# platine_gesamt_V03.net
KiCad netlist of a schematic drawn in EAGLE
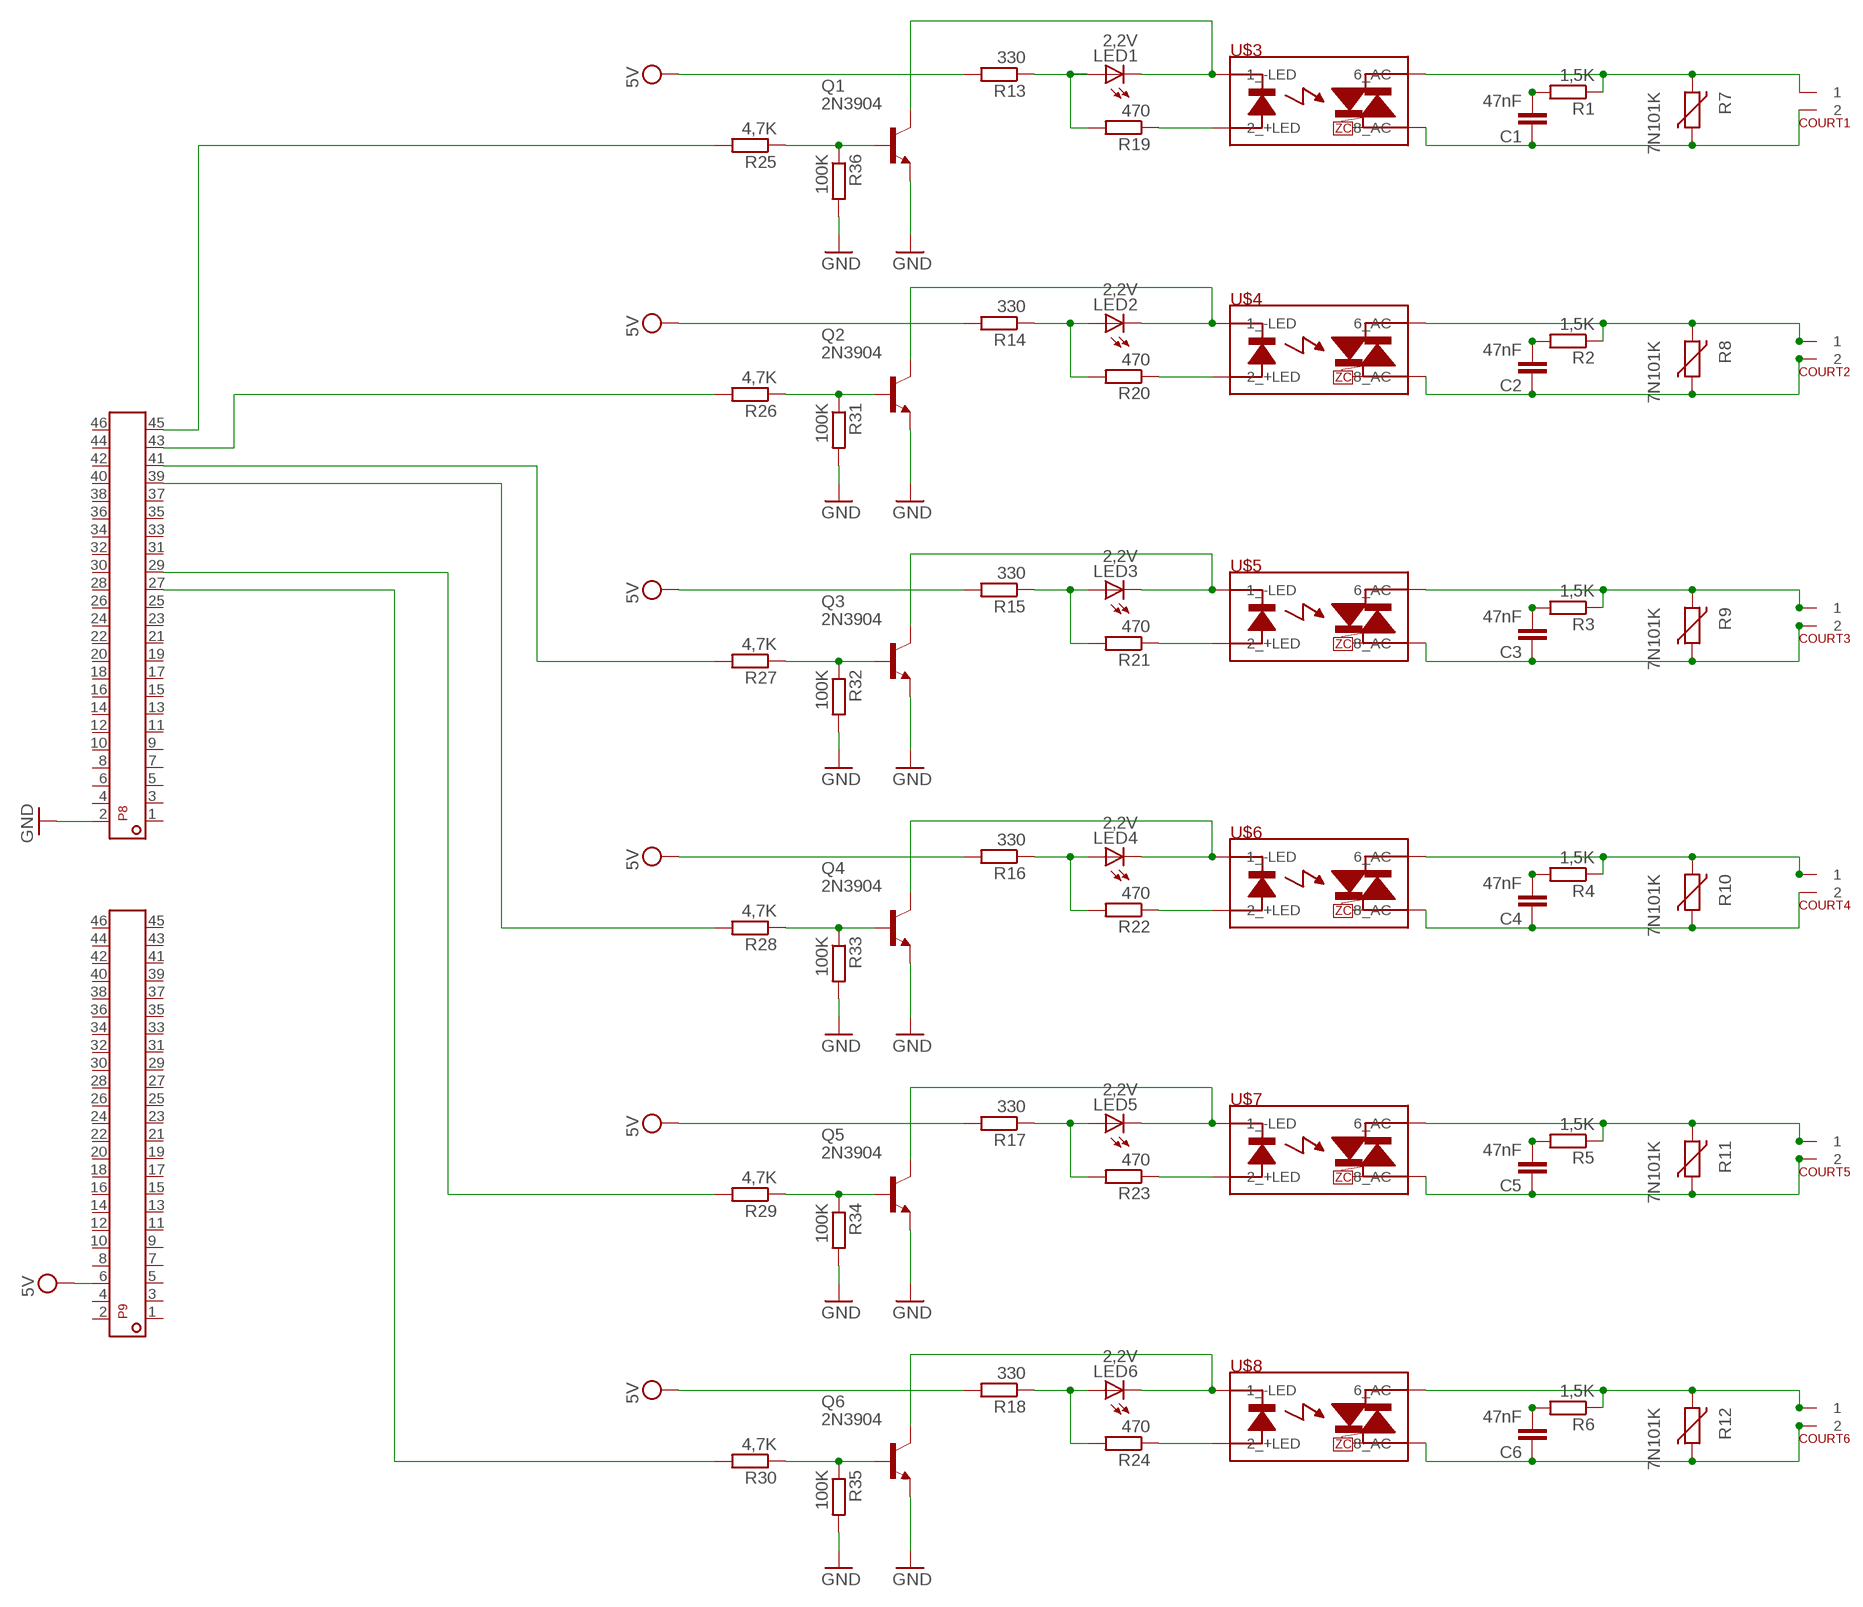
[diagram p0: schematic, sheet 1]

(export (version "E")
  (design (tool "Eeschema 10.0.6"))
  (components
    (comp (ref "C1")
      (value "47nF")
      (footprint "eagle-import:C7.5B3")
      (libsource (lib "eagle-import") (part "C7.5/3"))
    )
    (comp (ref "C2")
      (value "47nF")
      (footprint "eagle-import:C7.5B3")
      (libsource (lib "eagle-import") (part "C7.5/3"))
    )
    (comp (ref "C3")
      (value "47nF")
      (footprint "eagle-import:C7.5B3")
      (libsource (lib "eagle-import") (part "C7.5/3"))
    )
    (comp (ref "C4")
      (value "47nF")
      (footprint "eagle-import:C7.5B3")
      (libsource (lib "eagle-import") (part "C7.5/3"))
    )
    (comp (ref "C5")
      (value "47nF")
      (footprint "eagle-import:C7.5B3")
      (libsource (lib "eagle-import") (part "C7.5/3"))
    )
    (comp (ref "C6")
      (value "47nF")
      (footprint "eagle-import:C7.5B3")
      (libsource (lib "eagle-import") (part "C7.5/3"))
    )
    (comp (ref "COURT1")
      (value "KLEMMENBLOCK_2POL")
      (footprint "eagle-import:KLEMMENBLOCK_2POL")
      (libsource (lib "eagle-import") (part "KLEMMENBLOCK_2POL"))
    )
    (comp (ref "COURT2")
      (value "KLEMMENBLOCK_2POL")
      (footprint "eagle-import:KLEMMENBLOCK_2POL")
      (libsource (lib "eagle-import") (part "KLEMMENBLOCK_2POL"))
    )
    (comp (ref "COURT3")
      (value "KLEMMENBLOCK_2POL")
      (footprint "eagle-import:KLEMMENBLOCK_2POL")
      (libsource (lib "eagle-import") (part "KLEMMENBLOCK_2POL"))
    )
    (comp (ref "COURT4")
      (value "KLEMMENBLOCK_2POL")
      (footprint "eagle-import:KLEMMENBLOCK_2POL")
      (libsource (lib "eagle-import") (part "KLEMMENBLOCK_2POL"))
    )
    (comp (ref "COURT5")
      (value "KLEMMENBLOCK_2POL")
      (footprint "eagle-import:KLEMMENBLOCK_2POL")
      (libsource (lib "eagle-import") (part "KLEMMENBLOCK_2POL"))
    )
    (comp (ref "COURT6")
      (value "KLEMMENBLOCK_2POL")
      (footprint "eagle-import:KLEMMENBLOCK_2POL")
      (libsource (lib "eagle-import") (part "KLEMMENBLOCK_2POL"))
    )
    (comp (ref "LED1")
      (value "2,2V")
      (footprint "eagle-import:LED5MM")
      (libsource (lib "eagle-import") (part "LED5MM"))
    )
    (comp (ref "LED2")
      (value "2,2V")
      (footprint "eagle-import:LED5MM")
      (libsource (lib "eagle-import") (part "LED5MM"))
    )
    (comp (ref "LED3")
      (value "2,2V")
      (footprint "eagle-import:LED5MM")
      (libsource (lib "eagle-import") (part "LED5MM"))
    )
    (comp (ref "LED4")
      (value "2,2V")
      (footprint "eagle-import:LED5MM")
      (libsource (lib "eagle-import") (part "LED5MM"))
    )
    (comp (ref "LED5")
      (value "2,2V")
      (footprint "eagle-import:LED5MM")
      (libsource (lib "eagle-import") (part "LED5MM"))
    )
    (comp (ref "LED6")
      (value "2,2V")
      (footprint "eagle-import:LED5MM")
      (libsource (lib "eagle-import") (part "LED5MM"))
    )
    (comp (ref "P8")
      (value "FEMALE_HEADER_2X23")
      (footprint "eagle-import:FE23-2W")
      (libsource (lib "eagle-import") (part "FEMALE_HEADER_2X23"))
    )
    (comp (ref "P9")
      (value "FEMALE_HEADER_2X23")
      (footprint "eagle-import:FE23-2W")
      (libsource (lib "eagle-import") (part "FEMALE_HEADER_2X23"))
    )
    (comp (ref "Q1")
      (value "2N3904")
      (footprint "eagle-import:TO92")
      (libsource (lib "eagle-import") (part "2N3904"))
    )
    (comp (ref "Q2")
      (value "2N3904")
      (footprint "eagle-import:TO92")
      (libsource (lib "eagle-import") (part "2N3904"))
    )
    (comp (ref "Q3")
      (value "2N3904")
      (footprint "eagle-import:TO92")
      (libsource (lib "eagle-import") (part "2N3904"))
    )
    (comp (ref "Q4")
      (value "2N3904")
      (footprint "eagle-import:TO92")
      (libsource (lib "eagle-import") (part "2N3904"))
    )
    (comp (ref "Q5")
      (value "2N3904")
      (footprint "eagle-import:TO92")
      (libsource (lib "eagle-import") (part "2N3904"))
    )
    (comp (ref "Q6")
      (value "2N3904")
      (footprint "eagle-import:TO92")
      (libsource (lib "eagle-import") (part "2N3904"))
    )
    (comp (ref "R1")
      (value "1,5K")
      (footprint "eagle-import:0204_7")
      (libsource (lib "eagle-import") (part "R-EU_0204/7"))
    )
    (comp (ref "R2")
      (value "1,5K")
      (footprint "eagle-import:0204_7")
      (libsource (lib "eagle-import") (part "R-EU_0204/7"))
    )
    (comp (ref "R3")
      (value "1,5K")
      (footprint "eagle-import:0204_7")
      (libsource (lib "eagle-import") (part "R-EU_0204/7"))
    )
    (comp (ref "R4")
      (value "1,5K")
      (footprint "eagle-import:0204_7")
      (libsource (lib "eagle-import") (part "R-EU_0204/7"))
    )
    (comp (ref "R5")
      (value "1,5K")
      (footprint "eagle-import:0204_7")
      (libsource (lib "eagle-import") (part "R-EU_0204/7"))
    )
    (comp (ref "R6")
      (value "1,5K")
      (footprint "eagle-import:0204_7")
      (libsource (lib "eagle-import") (part "R-EU_0204/7"))
    )
    (comp (ref "R7")
      (value "7N101K")
      (footprint "eagle-import:R-5")
      (libsource (lib "eagle-import") (part "VARISTOR-5"))
    )
    (comp (ref "R8")
      (value "7N101K")
      (footprint "eagle-import:R-5")
      (libsource (lib "eagle-import") (part "VARISTOR-5"))
    )
    (comp (ref "R9")
      (value "7N101K")
      (footprint "eagle-import:R-5")
      (libsource (lib "eagle-import") (part "VARISTOR-5"))
    )
    (comp (ref "R10")
      (value "7N101K")
      (footprint "eagle-import:R-5")
      (libsource (lib "eagle-import") (part "VARISTOR-5"))
    )
    (comp (ref "R11")
      (value "7N101K")
      (footprint "eagle-import:R-5")
      (libsource (lib "eagle-import") (part "VARISTOR-5"))
    )
    (comp (ref "R12")
      (value "7N101K")
      (footprint "eagle-import:R-5")
      (libsource (lib "eagle-import") (part "VARISTOR-5"))
    )
    (comp (ref "R13")
      (value "330")
      (footprint "eagle-import:0204_7")
      (libsource (lib "eagle-import") (part "R-EU_0204/7"))
    )
    (comp (ref "R14")
      (value "330")
      (footprint "eagle-import:0204_7")
      (libsource (lib "eagle-import") (part "R-EU_0204/7"))
    )
    (comp (ref "R15")
      (value "330")
      (footprint "eagle-import:0204_7")
      (libsource (lib "eagle-import") (part "R-EU_0204/7"))
    )
    (comp (ref "R16")
      (value "330")
      (footprint "eagle-import:0204_7")
      (libsource (lib "eagle-import") (part "R-EU_0204/7"))
    )
    (comp (ref "R17")
      (value "330")
      (footprint "eagle-import:0204_7")
      (libsource (lib "eagle-import") (part "R-EU_0204/7"))
    )
    (comp (ref "R18")
      (value "330")
      (footprint "eagle-import:0204_7")
      (libsource (lib "eagle-import") (part "R-EU_0204/7"))
    )
    (comp (ref "R19")
      (value "470")
      (footprint "eagle-import:0204_7")
      (libsource (lib "eagle-import") (part "R-EU_0204/7"))
    )
    (comp (ref "R20")
      (value "470")
      (footprint "eagle-import:0204_7")
      (libsource (lib "eagle-import") (part "R-EU_0204/7"))
    )
    (comp (ref "R21")
      (value "470")
      (footprint "eagle-import:0204_7")
      (libsource (lib "eagle-import") (part "R-EU_0204/7"))
    )
    (comp (ref "R22")
      (value "470")
      (footprint "eagle-import:0204_7")
      (libsource (lib "eagle-import") (part "R-EU_0204/7"))
    )
    (comp (ref "R23")
      (value "470")
      (footprint "eagle-import:0204_7")
      (libsource (lib "eagle-import") (part "R-EU_0204/7"))
    )
    (comp (ref "R24")
      (value "470")
      (footprint "eagle-import:0204_7")
      (libsource (lib "eagle-import") (part "R-EU_0204/7"))
    )
    (comp (ref "R25")
      (value "4,7K")
      (footprint "eagle-import:0204_7")
      (libsource (lib "eagle-import") (part "R-EU_0204/7"))
    )
    (comp (ref "R26")
      (value "4,7K")
      (footprint "eagle-import:0204_7")
      (libsource (lib "eagle-import") (part "R-EU_0204/7"))
    )
    (comp (ref "R27")
      (value "4,7K")
      (footprint "eagle-import:0204_7")
      (libsource (lib "eagle-import") (part "R-EU_0204/7"))
    )
    (comp (ref "R28")
      (value "4,7K")
      (footprint "eagle-import:0204_7")
      (libsource (lib "eagle-import") (part "R-EU_0204/7"))
    )
    (comp (ref "R29")
      (value "4,7K")
      (footprint "eagle-import:0204_7")
      (libsource (lib "eagle-import") (part "R-EU_0204/7"))
    )
    (comp (ref "R30")
      (value "4,7K")
      (footprint "eagle-import:0204_7")
      (libsource (lib "eagle-import") (part "R-EU_0204/7"))
    )
    (comp (ref "R31")
      (value "100K")
      (footprint "eagle-import:0204_7")
      (libsource (lib "eagle-import") (part "R-EU_0204/7"))
    )
    (comp (ref "R32")
      (value "100K")
      (footprint "eagle-import:0204_7")
      (libsource (lib "eagle-import") (part "R-EU_0204/7"))
    )
    (comp (ref "R33")
      (value "100K")
      (footprint "eagle-import:0204_7")
      (libsource (lib "eagle-import") (part "R-EU_0204/7"))
    )
    (comp (ref "R34")
      (value "100K")
      (footprint "eagle-import:0204_7")
      (libsource (lib "eagle-import") (part "R-EU_0204/7"))
    )
    (comp (ref "R35")
      (value "100K")
      (footprint "eagle-import:0204_7")
      (libsource (lib "eagle-import") (part "R-EU_0204/7"))
    )
    (comp (ref "R36")
      (value "100K")
      (footprint "eagle-import:0204_7")
      (libsource (lib "eagle-import") (part "R-EU_0204/7"))
    )
    (comp (ref "U$3")
      (value "IXYS_PS1201_SSRSIP4/8")
      (footprint "eagle-import:S202S02")
      (libsource (lib "eagle-import") (part "IXYS_PS1201_SSRSIP4/8"))
    )
    (comp (ref "U$4")
      (value "IXYS_PS1201_SSRSIP4/8")
      (footprint "eagle-import:S202S02")
      (libsource (lib "eagle-import") (part "IXYS_PS1201_SSRSIP4/8"))
    )
    (comp (ref "U$5")
      (value "IXYS_PS1201_SSRSIP4/8")
      (footprint "eagle-import:S202S02")
      (libsource (lib "eagle-import") (part "IXYS_PS1201_SSRSIP4/8"))
    )
    (comp (ref "U$6")
      (value "IXYS_PS1201_SSRSIP4/8")
      (footprint "eagle-import:S202S02")
      (libsource (lib "eagle-import") (part "IXYS_PS1201_SSRSIP4/8"))
    )
    (comp (ref "U$7")
      (value "IXYS_PS1201_SSRSIP4/8")
      (footprint "eagle-import:S202S02")
      (libsource (lib "eagle-import") (part "IXYS_PS1201_SSRSIP4/8"))
    )
    (comp (ref "U$8")
      (value "IXYS_PS1201_SSRSIP4/8")
      (footprint "eagle-import:S202S02")
      (libsource (lib "eagle-import") (part "IXYS_PS1201_SSRSIP4/8"))
    )
  )
  (nets
    (net (code "1") (name "5V") (class "Default")
      (node (ref "P9") (pin "6") (pinfunction "6_6") (pintype "bidirectional"))
      (node (ref "R13") (pin "2") (pinfunction "2_2") (pintype "passive"))
      (node (ref "R14") (pin "2") (pinfunction "2_2") (pintype "passive"))
      (node (ref "R15") (pin "2") (pinfunction "2_2") (pintype "passive"))
      (node (ref "R16") (pin "2") (pinfunction "2_2") (pintype "passive"))
      (node (ref "R17") (pin "2") (pinfunction "2_2") (pintype "passive"))
      (node (ref "R18") (pin "2") (pinfunction "2_2") (pintype "passive"))
    )
    (net (code "2") (name "GND") (class "Default")
      (node (ref "P8") (pin "2") (pinfunction "2_2") (pintype "bidirectional"))
      (node (ref "Q1") (pin "3") (pinfunction "E_3") (pintype "passive"))
      (node (ref "Q2") (pin "3") (pinfunction "E_3") (pintype "passive"))
      (node (ref "Q3") (pin "3") (pinfunction "E_3") (pintype "passive"))
      (node (ref "Q4") (pin "3") (pinfunction "E_3") (pintype "passive"))
      (node (ref "Q5") (pin "3") (pinfunction "E_3") (pintype "passive"))
      (node (ref "Q6") (pin "3") (pinfunction "E_3") (pintype "passive"))
      (node (ref "R31") (pin "2") (pinfunction "2_2") (pintype "passive"))
      (node (ref "R32") (pin "2") (pinfunction "2_2") (pintype "passive"))
      (node (ref "R33") (pin "2") (pinfunction "2_2") (pintype "passive"))
      (node (ref "R34") (pin "2") (pinfunction "2_2") (pintype "passive"))
      (node (ref "R35") (pin "2") (pinfunction "2_2") (pintype "passive"))
      (node (ref "R36") (pin "2") (pinfunction "2_2") (pintype "passive"))
    )
    (net (code "3") (name "Net-(C1-Pad2)") (class "Default")
      (node (ref "C1") (pin "2") (pinfunction "2_2") (pintype "passive"))
      (node (ref "R1") (pin "2") (pinfunction "2_2") (pintype "passive"))
    )
    (net (code "4") (name "Net-(C2-Pad2)") (class "Default")
      (node (ref "C2") (pin "2") (pinfunction "2_2") (pintype "passive"))
      (node (ref "R2") (pin "2") (pinfunction "2_2") (pintype "passive"))
    )
    (net (code "5") (name "Net-(C3-Pad2)") (class "Default")
      (node (ref "C3") (pin "2") (pinfunction "2_2") (pintype "passive"))
      (node (ref "R3") (pin "2") (pinfunction "2_2") (pintype "passive"))
    )
    (net (code "6") (name "Net-(C4-Pad2)") (class "Default")
      (node (ref "C4") (pin "2") (pinfunction "2_2") (pintype "passive"))
      (node (ref "R4") (pin "2") (pinfunction "2_2") (pintype "passive"))
    )
    (net (code "7") (name "Net-(C5-Pad2)") (class "Default")
      (node (ref "C5") (pin "2") (pinfunction "2_2") (pintype "passive"))
      (node (ref "R5") (pin "2") (pinfunction "2_2") (pintype "passive"))
    )
    (net (code "8") (name "Net-(C6-Pad2)") (class "Default")
      (node (ref "C6") (pin "2") (pinfunction "2_2") (pintype "passive"))
      (node (ref "R6") (pin "2") (pinfunction "2_2") (pintype "passive"))
    )
    (net (code "9") (name "Net-(LED1-C)") (class "Default")
      (node (ref "LED1") (pin "K") (pinfunction "C_K") (pintype "passive"))
      (node (ref "Q1") (pin "1") (pinfunction "C_1") (pintype "passive"))
      (node (ref "U$3") (pin "1") (pinfunction "1_-LED_1") (pintype "bidirectional"))
    )
    (net (code "10") (name "Net-(LED1-PadA)") (class "Default")
      (node (ref "LED1") (pin "A") (pinfunction "A_A") (pintype "passive"))
      (node (ref "R13") (pin "1") (pinfunction "1_1") (pintype "passive"))
      (node (ref "R19") (pin "2") (pinfunction "2_2") (pintype "passive"))
    )
    (net (code "11") (name "Net-(LED2-C)") (class "Default")
      (node (ref "LED2") (pin "K") (pinfunction "C_K") (pintype "passive"))
      (node (ref "Q2") (pin "1") (pinfunction "C_1") (pintype "passive"))
      (node (ref "U$4") (pin "1") (pinfunction "1_-LED_1") (pintype "bidirectional"))
    )
    (net (code "12") (name "Net-(LED2-PadA)") (class "Default")
      (node (ref "LED2") (pin "A") (pinfunction "A_A") (pintype "passive"))
      (node (ref "R14") (pin "1") (pinfunction "1_1") (pintype "passive"))
      (node (ref "R20") (pin "2") (pinfunction "2_2") (pintype "passive"))
    )
    (net (code "13") (name "Net-(LED3-C)") (class "Default")
      (node (ref "LED3") (pin "K") (pinfunction "C_K") (pintype "passive"))
      (node (ref "Q3") (pin "1") (pinfunction "C_1") (pintype "passive"))
      (node (ref "U$5") (pin "1") (pinfunction "1_-LED_1") (pintype "bidirectional"))
    )
    (net (code "14") (name "Net-(LED3-PadA)") (class "Default")
      (node (ref "LED3") (pin "A") (pinfunction "A_A") (pintype "passive"))
      (node (ref "R15") (pin "1") (pinfunction "1_1") (pintype "passive"))
      (node (ref "R21") (pin "2") (pinfunction "2_2") (pintype "passive"))
    )
    (net (code "15") (name "Net-(LED4-C)") (class "Default")
      (node (ref "LED4") (pin "K") (pinfunction "C_K") (pintype "passive"))
      (node (ref "Q4") (pin "1") (pinfunction "C_1") (pintype "passive"))
      (node (ref "U$6") (pin "1") (pinfunction "1_-LED_1") (pintype "bidirectional"))
    )
    (net (code "16") (name "Net-(LED4-PadA)") (class "Default")
      (node (ref "LED4") (pin "A") (pinfunction "A_A") (pintype "passive"))
      (node (ref "R16") (pin "1") (pinfunction "1_1") (pintype "passive"))
      (node (ref "R22") (pin "2") (pinfunction "2_2") (pintype "passive"))
    )
    (net (code "17") (name "Net-(LED5-C)") (class "Default")
      (node (ref "LED5") (pin "K") (pinfunction "C_K") (pintype "passive"))
      (node (ref "Q5") (pin "1") (pinfunction "C_1") (pintype "passive"))
      (node (ref "U$7") (pin "1") (pinfunction "1_-LED_1") (pintype "bidirectional"))
    )
    (net (code "18") (name "Net-(LED5-PadA)") (class "Default")
      (node (ref "LED5") (pin "A") (pinfunction "A_A") (pintype "passive"))
      (node (ref "R17") (pin "1") (pinfunction "1_1") (pintype "passive"))
      (node (ref "R23") (pin "2") (pinfunction "2_2") (pintype "passive"))
    )
    (net (code "19") (name "Net-(LED6-C)") (class "Default")
      (node (ref "LED6") (pin "K") (pinfunction "C_K") (pintype "passive"))
      (node (ref "Q6") (pin "1") (pinfunction "C_1") (pintype "passive"))
      (node (ref "U$8") (pin "1") (pinfunction "1_-LED_1") (pintype "bidirectional"))
    )
    (net (code "20") (name "Net-(LED6-PadA)") (class "Default")
      (node (ref "LED6") (pin "A") (pinfunction "A_A") (pintype "passive"))
      (node (ref "R18") (pin "1") (pinfunction "1_1") (pintype "passive"))
      (node (ref "R24") (pin "2") (pinfunction "2_2") (pintype "passive"))
    )
    (net (code "21") (name "Net-(P8-Pad27)") (class "Default")
      (node (ref "P8") (pin "27") (pinfunction "27_27") (pintype "bidirectional"))
      (node (ref "R30") (pin "2") (pinfunction "2_2") (pintype "passive"))
    )
    (net (code "22") (name "Net-(P8-Pad29)") (class "Default")
      (node (ref "P8") (pin "29") (pinfunction "29_29") (pintype "bidirectional"))
      (node (ref "R29") (pin "2") (pinfunction "2_2") (pintype "passive"))
    )
    (net (code "23") (name "Net-(P8-Pad39)") (class "Default")
      (node (ref "P8") (pin "39") (pinfunction "39_39") (pintype "bidirectional"))
      (node (ref "R28") (pin "2") (pinfunction "2_2") (pintype "passive"))
    )
    (net (code "24") (name "Net-(P8-Pad41)") (class "Default")
      (node (ref "P8") (pin "41") (pinfunction "41_41") (pintype "bidirectional"))
      (node (ref "R27") (pin "2") (pinfunction "2_2") (pintype "passive"))
    )
    (net (code "25") (name "Net-(P8-Pad43)") (class "Default")
      (node (ref "P8") (pin "43") (pinfunction "43_43") (pintype "bidirectional"))
      (node (ref "R26") (pin "2") (pinfunction "2_2") (pintype "passive"))
    )
    (net (code "26") (name "Net-(P8-Pad45)") (class "Default")
      (node (ref "P8") (pin "45") (pinfunction "45_45") (pintype "bidirectional"))
      (node (ref "R25") (pin "2") (pinfunction "2_2") (pintype "passive"))
    )
    (net (code "27") (name "Net-(Q1-B)") (class "Default")
      (node (ref "Q1") (pin "2") (pinfunction "B_2") (pintype "passive"))
      (node (ref "R25") (pin "1") (pinfunction "1_1") (pintype "passive"))
      (node (ref "R36") (pin "1") (pinfunction "1_1") (pintype "passive"))
    )
    (net (code "28") (name "Net-(Q2-B)") (class "Default")
      (node (ref "Q2") (pin "2") (pinfunction "B_2") (pintype "passive"))
      (node (ref "R26") (pin "1") (pinfunction "1_1") (pintype "passive"))
      (node (ref "R31") (pin "1") (pinfunction "1_1") (pintype "passive"))
    )
    (net (code "29") (name "Net-(Q3-B)") (class "Default")
      (node (ref "Q3") (pin "2") (pinfunction "B_2") (pintype "passive"))
      (node (ref "R27") (pin "1") (pinfunction "1_1") (pintype "passive"))
      (node (ref "R32") (pin "1") (pinfunction "1_1") (pintype "passive"))
    )
    (net (code "30") (name "Net-(Q4-B)") (class "Default")
      (node (ref "Q4") (pin "2") (pinfunction "B_2") (pintype "passive"))
      (node (ref "R28") (pin "1") (pinfunction "1_1") (pintype "passive"))
      (node (ref "R33") (pin "1") (pinfunction "1_1") (pintype "passive"))
    )
    (net (code "31") (name "Net-(Q5-B)") (class "Default")
      (node (ref "Q5") (pin "2") (pinfunction "B_2") (pintype "passive"))
      (node (ref "R29") (pin "1") (pinfunction "1_1") (pintype "passive"))
      (node (ref "R34") (pin "1") (pinfunction "1_1") (pintype "passive"))
    )
    (net (code "32") (name "Net-(Q6-B)") (class "Default")
      (node (ref "Q6") (pin "2") (pinfunction "B_2") (pintype "passive"))
      (node (ref "R30") (pin "1") (pinfunction "1_1") (pintype "passive"))
      (node (ref "R35") (pin "1") (pinfunction "1_1") (pintype "passive"))
    )
    (net (code "33") (name "Net-(U$3-2_+LED)") (class "Default")
      (node (ref "R19") (pin "1") (pinfunction "1_1") (pintype "passive"))
      (node (ref "U$3") (pin "2") (pinfunction "2_+LED_2") (pintype "bidirectional"))
    )
    (net (code "34") (name "Net-(U$3-6_AC)") (class "Default")
      (node (ref "COURT1") (pin "1") (pinfunction "1_1") (pintype "bidirectional"))
      (node (ref "R1") (pin "1") (pinfunction "1_1") (pintype "passive"))
      (node (ref "R7") (pin "2") (pinfunction "2_2") (pintype "passive"))
      (node (ref "U$3") (pin "6") (pinfunction "6_AC_6") (pintype "bidirectional"))
    )
    (net (code "35") (name "Net-(U$3-8_AC)") (class "Default")
      (node (ref "C1") (pin "1") (pinfunction "1_1") (pintype "passive"))
      (node (ref "COURT1") (pin "2") (pinfunction "2_2") (pintype "bidirectional"))
      (node (ref "R7") (pin "1") (pinfunction "1_1") (pintype "passive"))
      (node (ref "U$3") (pin "8") (pinfunction "8_AC_8") (pintype "bidirectional"))
    )
    (net (code "36") (name "Net-(U$4-2_+LED)") (class "Default")
      (node (ref "R20") (pin "1") (pinfunction "1_1") (pintype "passive"))
      (node (ref "U$4") (pin "2") (pinfunction "2_+LED_2") (pintype "bidirectional"))
    )
    (net (code "37") (name "Net-(U$4-6_AC)") (class "Default")
      (node (ref "COURT2") (pin "1") (pinfunction "1_1") (pintype "bidirectional"))
      (node (ref "R2") (pin "1") (pinfunction "1_1") (pintype "passive"))
      (node (ref "R8") (pin "2") (pinfunction "2_2") (pintype "passive"))
      (node (ref "U$4") (pin "6") (pinfunction "6_AC_6") (pintype "bidirectional"))
    )
    (net (code "38") (name "Net-(U$4-8_AC)") (class "Default")
      (node (ref "C2") (pin "1") (pinfunction "1_1") (pintype "passive"))
      (node (ref "COURT2") (pin "2") (pinfunction "2_2") (pintype "bidirectional"))
      (node (ref "R8") (pin "1") (pinfunction "1_1") (pintype "passive"))
      (node (ref "U$4") (pin "8") (pinfunction "8_AC_8") (pintype "bidirectional"))
    )
    (net (code "39") (name "Net-(U$5-2_+LED)") (class "Default")
      (node (ref "R21") (pin "1") (pinfunction "1_1") (pintype "passive"))
      (node (ref "U$5") (pin "2") (pinfunction "2_+LED_2") (pintype "bidirectional"))
    )
    (net (code "40") (name "Net-(U$5-6_AC)") (class "Default")
      (node (ref "COURT3") (pin "1") (pinfunction "1_1") (pintype "bidirectional"))
      (node (ref "R3") (pin "1") (pinfunction "1_1") (pintype "passive"))
      (node (ref "R9") (pin "2") (pinfunction "2_2") (pintype "passive"))
      (node (ref "U$5") (pin "6") (pinfunction "6_AC_6") (pintype "bidirectional"))
    )
    (net (code "41") (name "Net-(U$5-8_AC)") (class "Default")
      (node (ref "C3") (pin "1") (pinfunction "1_1") (pintype "passive"))
      (node (ref "COURT3") (pin "2") (pinfunction "2_2") (pintype "bidirectional"))
      (node (ref "R9") (pin "1") (pinfunction "1_1") (pintype "passive"))
      (node (ref "U$5") (pin "8") (pinfunction "8_AC_8") (pintype "bidirectional"))
    )
    (net (code "42") (name "Net-(U$6-2_+LED)") (class "Default")
      (node (ref "R22") (pin "1") (pinfunction "1_1") (pintype "passive"))
      (node (ref "U$6") (pin "2") (pinfunction "2_+LED_2") (pintype "bidirectional"))
    )
    (net (code "43") (name "Net-(U$6-6_AC)") (class "Default")
      (node (ref "COURT4") (pin "1") (pinfunction "1_1") (pintype "bidirectional"))
      (node (ref "R10") (pin "2") (pinfunction "2_2") (pintype "passive"))
      (node (ref "R4") (pin "1") (pinfunction "1_1") (pintype "passive"))
      (node (ref "U$6") (pin "6") (pinfunction "6_AC_6") (pintype "bidirectional"))
    )
    (net (code "44") (name "Net-(U$6-8_AC)") (class "Default")
      (node (ref "C4") (pin "1") (pinfunction "1_1") (pintype "passive"))
      (node (ref "COURT4") (pin "2") (pinfunction "2_2") (pintype "bidirectional"))
      (node (ref "R10") (pin "1") (pinfunction "1_1") (pintype "passive"))
      (node (ref "U$6") (pin "8") (pinfunction "8_AC_8") (pintype "bidirectional"))
    )
    (net (code "45") (name "Net-(U$7-2_+LED)") (class "Default")
      (node (ref "R23") (pin "1") (pinfunction "1_1") (pintype "passive"))
      (node (ref "U$7") (pin "2") (pinfunction "2_+LED_2") (pintype "bidirectional"))
    )
    (net (code "46") (name "Net-(U$7-6_AC)") (class "Default")
      (node (ref "COURT5") (pin "1") (pinfunction "1_1") (pintype "bidirectional"))
      (node (ref "R11") (pin "2") (pinfunction "2_2") (pintype "passive"))
      (node (ref "R5") (pin "1") (pinfunction "1_1") (pintype "passive"))
      (node (ref "U$7") (pin "6") (pinfunction "6_AC_6") (pintype "bidirectional"))
    )
    (net (code "47") (name "Net-(U$7-8_AC)") (class "Default")
      (node (ref "C5") (pin "1") (pinfunction "1_1") (pintype "passive"))
      (node (ref "COURT5") (pin "2") (pinfunction "2_2") (pintype "bidirectional"))
      (node (ref "R11") (pin "1") (pinfunction "1_1") (pintype "passive"))
      (node (ref "U$7") (pin "8") (pinfunction "8_AC_8") (pintype "bidirectional"))
    )
    (net (code "48") (name "Net-(U$8-2_+LED)") (class "Default")
      (node (ref "R24") (pin "1") (pinfunction "1_1") (pintype "passive"))
      (node (ref "U$8") (pin "2") (pinfunction "2_+LED_2") (pintype "bidirectional"))
    )
    (net (code "49") (name "Net-(U$8-6_AC)") (class "Default")
      (node (ref "COURT6") (pin "1") (pinfunction "1_1") (pintype "bidirectional"))
      (node (ref "R12") (pin "2") (pinfunction "2_2") (pintype "passive"))
      (node (ref "R6") (pin "1") (pinfunction "1_1") (pintype "passive"))
      (node (ref "U$8") (pin "6") (pinfunction "6_AC_6") (pintype "bidirectional"))
    )
    (net (code "50") (name "Net-(U$8-8_AC)") (class "Default")
      (node (ref "C6") (pin "1") (pinfunction "1_1") (pintype "passive"))
      (node (ref "COURT6") (pin "2") (pinfunction "2_2") (pintype "bidirectional"))
      (node (ref "R12") (pin "1") (pinfunction "1_1") (pintype "passive"))
      (node (ref "U$8") (pin "8") (pinfunction "8_AC_8") (pintype "bidirectional"))
    )
    (net (code "51") (name "unconnected-(P8-Pad1)") (class "Default")
      (node (ref "P8") (pin "1") (pinfunction "1_1") (pintype "bidirectional"))
    )
    (net (code "52") (name "unconnected-(P8-Pad3)") (class "Default")
      (node (ref "P8") (pin "3") (pinfunction "3_3") (pintype "bidirectional"))
    )
    (net (code "53") (name "unconnected-(P8-Pad4)") (class "Default")
      (node (ref "P8") (pin "4") (pinfunction "4_4") (pintype "bidirectional"))
    )
    (net (code "54") (name "unconnected-(P8-Pad5)") (class "Default")
      (node (ref "P8") (pin "5") (pinfunction "5_5") (pintype "bidirectional"))
    )
    (net (code "55") (name "unconnected-(P8-Pad6)") (class "Default")
      (node (ref "P8") (pin "6") (pinfunction "6_6") (pintype "bidirectional"))
    )
    (net (code "56") (name "unconnected-(P8-Pad7)") (class "Default")
      (node (ref "P8") (pin "7") (pinfunction "7_7") (pintype "bidirectional"))
    )
    (net (code "57") (name "unconnected-(P8-Pad8)") (class "Default")
      (node (ref "P8") (pin "8") (pinfunction "8_8") (pintype "bidirectional"))
    )
    (net (code "58") (name "unconnected-(P8-Pad9)") (class "Default")
      (node (ref "P8") (pin "9") (pinfunction "9_9") (pintype "bidirectional"))
    )
    (net (code "59") (name "unconnected-(P8-Pad10)") (class "Default")
      (node (ref "P8") (pin "10") (pinfunction "10_10") (pintype "bidirectional"))
    )
    (net (code "60") (name "unconnected-(P8-Pad11)") (class "Default")
      (node (ref "P8") (pin "11") (pinfunction "11_11") (pintype "bidirectional"))
    )
    (net (code "61") (name "unconnected-(P8-Pad12)") (class "Default")
      (node (ref "P8") (pin "12") (pinfunction "12_12") (pintype "bidirectional"))
    )
    (net (code "62") (name "unconnected-(P8-Pad13)") (class "Default")
      (node (ref "P8") (pin "13") (pinfunction "13_13") (pintype "bidirectional"))
    )
    (net (code "63") (name "unconnected-(P8-Pad14)") (class "Default")
      (node (ref "P8") (pin "14") (pinfunction "14_14") (pintype "bidirectional"))
    )
    (net (code "64") (name "unconnected-(P8-Pad15)") (class "Default")
      (node (ref "P8") (pin "15") (pinfunction "15_15") (pintype "bidirectional"))
    )
    (net (code "65") (name "unconnected-(P8-Pad16)") (class "Default")
      (node (ref "P8") (pin "16") (pinfunction "16_16") (pintype "bidirectional"))
    )
    (net (code "66") (name "unconnected-(P8-Pad17)") (class "Default")
      (node (ref "P8") (pin "17") (pinfunction "17_17") (pintype "bidirectional"))
    )
    (net (code "67") (name "unconnected-(P8-Pad18)") (class "Default")
      (node (ref "P8") (pin "18") (pinfunction "18_18") (pintype "bidirectional"))
    )
    (net (code "68") (name "unconnected-(P8-Pad19)") (class "Default")
      (node (ref "P8") (pin "19") (pinfunction "19_19") (pintype "bidirectional"))
    )
    (net (code "69") (name "unconnected-(P8-Pad20)") (class "Default")
      (node (ref "P8") (pin "20") (pinfunction "20_20") (pintype "bidirectional"))
    )
    (net (code "70") (name "unconnected-(P8-Pad21)") (class "Default")
      (node (ref "P8") (pin "21") (pinfunction "21_21") (pintype "bidirectional"))
    )
    (net (code "71") (name "unconnected-(P8-Pad22)") (class "Default")
      (node (ref "P8") (pin "22") (pinfunction "22_22") (pintype "bidirectional"))
    )
    (net (code "72") (name "unconnected-(P8-Pad23)") (class "Default")
      (node (ref "P8") (pin "23") (pinfunction "23_23") (pintype "bidirectional"))
    )
    (net (code "73") (name "unconnected-(P8-Pad24)") (class "Default")
      (node (ref "P8") (pin "24") (pinfunction "24_24") (pintype "bidirectional"))
    )
    (net (code "74") (name "unconnected-(P8-Pad25)") (class "Default")
      (node (ref "P8") (pin "25") (pinfunction "25_25") (pintype "bidirectional"))
    )
    (net (code "75") (name "unconnected-(P8-Pad26)") (class "Default")
      (node (ref "P8") (pin "26") (pinfunction "26_26") (pintype "bidirectional"))
    )
    (net (code "76") (name "unconnected-(P8-Pad28)") (class "Default")
      (node (ref "P8") (pin "28") (pinfunction "28_28") (pintype "bidirectional"))
    )
    (net (code "77") (name "unconnected-(P8-Pad30)") (class "Default")
      (node (ref "P8") (pin "30") (pinfunction "30_30") (pintype "bidirectional"))
    )
    (net (code "78") (name "unconnected-(P8-Pad31)") (class "Default")
      (node (ref "P8") (pin "31") (pinfunction "31_31") (pintype "bidirectional"))
    )
    (net (code "79") (name "unconnected-(P8-Pad32)") (class "Default")
      (node (ref "P8") (pin "32") (pinfunction "32_32") (pintype "bidirectional"))
    )
    (net (code "80") (name "unconnected-(P8-Pad33)") (class "Default")
      (node (ref "P8") (pin "33") (pinfunction "33_33") (pintype "bidirectional"))
    )
    (net (code "81") (name "unconnected-(P8-Pad34)") (class "Default")
      (node (ref "P8") (pin "34") (pinfunction "34_34") (pintype "bidirectional"))
    )
    (net (code "82") (name "unconnected-(P8-Pad35)") (class "Default")
      (node (ref "P8") (pin "35") (pinfunction "35_35") (pintype "bidirectional"))
    )
    (net (code "83") (name "unconnected-(P8-Pad36)") (class "Default")
      (node (ref "P8") (pin "36") (pinfunction "36_36") (pintype "bidirectional"))
    )
    (net (code "84") (name "unconnected-(P8-Pad37)") (class "Default")
      (node (ref "P8") (pin "37") (pinfunction "37_37") (pintype "bidirectional"))
    )
    (net (code "85") (name "unconnected-(P8-Pad38)") (class "Default")
      (node (ref "P8") (pin "38") (pinfunction "38_38") (pintype "bidirectional"))
    )
    (net (code "86") (name "unconnected-(P8-Pad40)") (class "Default")
      (node (ref "P8") (pin "40") (pinfunction "40_40") (pintype "bidirectional"))
    )
    (net (code "87") (name "unconnected-(P8-Pad42)") (class "Default")
      (node (ref "P8") (pin "42") (pinfunction "42_42") (pintype "bidirectional"))
    )
    (net (code "88") (name "unconnected-(P8-Pad44)") (class "Default")
      (node (ref "P8") (pin "44") (pinfunction "44_44") (pintype "bidirectional"))
    )
    (net (code "89") (name "unconnected-(P8-Pad46)") (class "Default")
      (node (ref "P8") (pin "46") (pinfunction "46_46") (pintype "bidirectional"))
    )
    (net (code "90") (name "unconnected-(P9-Pad1)") (class "Default")
      (node (ref "P9") (pin "1") (pinfunction "1_1") (pintype "bidirectional"))
    )
    (net (code "91") (name "unconnected-(P9-Pad2)") (class "Default")
      (node (ref "P9") (pin "2") (pinfunction "2_2") (pintype "bidirectional"))
    )
    (net (code "92") (name "unconnected-(P9-Pad3)") (class "Default")
      (node (ref "P9") (pin "3") (pinfunction "3_3") (pintype "bidirectional"))
    )
    (net (code "93") (name "unconnected-(P9-Pad4)") (class "Default")
      (node (ref "P9") (pin "4") (pinfunction "4_4") (pintype "bidirectional"))
    )
    (net (code "94") (name "unconnected-(P9-Pad5)") (class "Default")
      (node (ref "P9") (pin "5") (pinfunction "5_5") (pintype "bidirectional"))
    )
    (net (code "95") (name "unconnected-(P9-Pad7)") (class "Default")
      (node (ref "P9") (pin "7") (pinfunction "7_7") (pintype "bidirectional"))
    )
    (net (code "96") (name "unconnected-(P9-Pad8)") (class "Default")
      (node (ref "P9") (pin "8") (pinfunction "8_8") (pintype "bidirectional"))
    )
    (net (code "97") (name "unconnected-(P9-Pad9)") (class "Default")
      (node (ref "P9") (pin "9") (pinfunction "9_9") (pintype "bidirectional"))
    )
    (net (code "98") (name "unconnected-(P9-Pad10)") (class "Default")
      (node (ref "P9") (pin "10") (pinfunction "10_10") (pintype "bidirectional"))
    )
    (net (code "99") (name "unconnected-(P9-Pad11)") (class "Default")
      (node (ref "P9") (pin "11") (pinfunction "11_11") (pintype "bidirectional"))
    )
    (net (code "100") (name "unconnected-(P9-Pad12)") (class "Default")
      (node (ref "P9") (pin "12") (pinfunction "12_12") (pintype "bidirectional"))
    )
    (net (code "101") (name "unconnected-(P9-Pad13)") (class "Default")
      (node (ref "P9") (pin "13") (pinfunction "13_13") (pintype "bidirectional"))
    )
    (net (code "102") (name "unconnected-(P9-Pad14)") (class "Default")
      (node (ref "P9") (pin "14") (pinfunction "14_14") (pintype "bidirectional"))
    )
    (net (code "103") (name "unconnected-(P9-Pad15)") (class "Default")
      (node (ref "P9") (pin "15") (pinfunction "15_15") (pintype "bidirectional"))
    )
    (net (code "104") (name "unconnected-(P9-Pad16)") (class "Default")
      (node (ref "P9") (pin "16") (pinfunction "16_16") (pintype "bidirectional"))
    )
    (net (code "105") (name "unconnected-(P9-Pad17)") (class "Default")
      (node (ref "P9") (pin "17") (pinfunction "17_17") (pintype "bidirectional"))
    )
    (net (code "106") (name "unconnected-(P9-Pad18)") (class "Default")
      (node (ref "P9") (pin "18") (pinfunction "18_18") (pintype "bidirectional"))
    )
    (net (code "107") (name "unconnected-(P9-Pad19)") (class "Default")
      (node (ref "P9") (pin "19") (pinfunction "19_19") (pintype "bidirectional"))
    )
    (net (code "108") (name "unconnected-(P9-Pad20)") (class "Default")
      (node (ref "P9") (pin "20") (pinfunction "20_20") (pintype "bidirectional"))
    )
    (net (code "109") (name "unconnected-(P9-Pad21)") (class "Default")
      (node (ref "P9") (pin "21") (pinfunction "21_21") (pintype "bidirectional"))
    )
    (net (code "110") (name "unconnected-(P9-Pad22)") (class "Default")
      (node (ref "P9") (pin "22") (pinfunction "22_22") (pintype "bidirectional"))
    )
    (net (code "111") (name "unconnected-(P9-Pad23)") (class "Default")
      (node (ref "P9") (pin "23") (pinfunction "23_23") (pintype "bidirectional"))
    )
    (net (code "112") (name "unconnected-(P9-Pad24)") (class "Default")
      (node (ref "P9") (pin "24") (pinfunction "24_24") (pintype "bidirectional"))
    )
    (net (code "113") (name "unconnected-(P9-Pad25)") (class "Default")
      (node (ref "P9") (pin "25") (pinfunction "25_25") (pintype "bidirectional"))
    )
    (net (code "114") (name "unconnected-(P9-Pad26)") (class "Default")
      (node (ref "P9") (pin "26") (pinfunction "26_26") (pintype "bidirectional"))
    )
    (net (code "115") (name "unconnected-(P9-Pad27)") (class "Default")
      (node (ref "P9") (pin "27") (pinfunction "27_27") (pintype "bidirectional"))
    )
    (net (code "116") (name "unconnected-(P9-Pad28)") (class "Default")
      (node (ref "P9") (pin "28") (pinfunction "28_28") (pintype "bidirectional"))
    )
    (net (code "117") (name "unconnected-(P9-Pad29)") (class "Default")
      (node (ref "P9") (pin "29") (pinfunction "29_29") (pintype "bidirectional"))
    )
    (net (code "118") (name "unconnected-(P9-Pad30)") (class "Default")
      (node (ref "P9") (pin "30") (pinfunction "30_30") (pintype "bidirectional"))
    )
    (net (code "119") (name "unconnected-(P9-Pad31)") (class "Default")
      (node (ref "P9") (pin "31") (pinfunction "31_31") (pintype "bidirectional"))
    )
    (net (code "120") (name "unconnected-(P9-Pad32)") (class "Default")
      (node (ref "P9") (pin "32") (pinfunction "32_32") (pintype "bidirectional"))
    )
    (net (code "121") (name "unconnected-(P9-Pad33)") (class "Default")
      (node (ref "P9") (pin "33") (pinfunction "33_33") (pintype "bidirectional"))
    )
    (net (code "122") (name "unconnected-(P9-Pad34)") (class "Default")
      (node (ref "P9") (pin "34") (pinfunction "34_34") (pintype "bidirectional"))
    )
    (net (code "123") (name "unconnected-(P9-Pad35)") (class "Default")
      (node (ref "P9") (pin "35") (pinfunction "35_35") (pintype "bidirectional"))
    )
    (net (code "124") (name "unconnected-(P9-Pad36)") (class "Default")
      (node (ref "P9") (pin "36") (pinfunction "36_36") (pintype "bidirectional"))
    )
    (net (code "125") (name "unconnected-(P9-Pad37)") (class "Default")
      (node (ref "P9") (pin "37") (pinfunction "37_37") (pintype "bidirectional"))
    )
    (net (code "126") (name "unconnected-(P9-Pad38)") (class "Default")
      (node (ref "P9") (pin "38") (pinfunction "38_38") (pintype "bidirectional"))
    )
    (net (code "127") (name "unconnected-(P9-Pad39)") (class "Default")
      (node (ref "P9") (pin "39") (pinfunction "39_39") (pintype "bidirectional"))
    )
    (net (code "128") (name "unconnected-(P9-Pad40)") (class "Default")
      (node (ref "P9") (pin "40") (pinfunction "40_40") (pintype "bidirectional"))
    )
    (net (code "129") (name "unconnected-(P9-Pad41)") (class "Default")
      (node (ref "P9") (pin "41") (pinfunction "41_41") (pintype "bidirectional"))
    )
    (net (code "130") (name "unconnected-(P9-Pad42)") (class "Default")
      (node (ref "P9") (pin "42") (pinfunction "42_42") (pintype "bidirectional"))
    )
    (net (code "131") (name "unconnected-(P9-Pad43)") (class "Default")
      (node (ref "P9") (pin "43") (pinfunction "43_43") (pintype "bidirectional"))
    )
    (net (code "132") (name "unconnected-(P9-Pad44)") (class "Default")
      (node (ref "P9") (pin "44") (pinfunction "44_44") (pintype "bidirectional"))
    )
    (net (code "133") (name "unconnected-(P9-Pad45)") (class "Default")
      (node (ref "P9") (pin "45") (pinfunction "45_45") (pintype "bidirectional"))
    )
    (net (code "134") (name "unconnected-(P9-Pad46)") (class "Default")
      (node (ref "P9") (pin "46") (pinfunction "46_46") (pintype "bidirectional"))
    )
  )
)
